# VL53L0X.net
KiCad netlist of a schematic drawn in Altium Designer
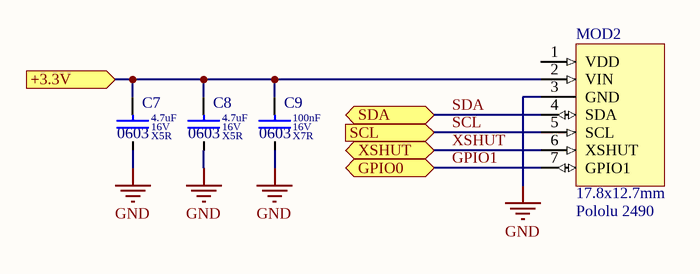
[diagram p0: VL53L0X.SchDoc]

(export (version "E")
  (design (tool "Eeschema 10.0.6"))
  (components
    (comp (ref "C7")
      (value "4.7uF")
      (footprint "C_0603_1608")
      (description "Capacitor")
      (fields
        (field (name "DIELECTRIC") "X5R")
        (field (name "VOLTAGE") "16V")
        (field (name "SCH_FOOTPRINT") "0603")
        (field (name "PART NUMBER") "C_4.7uF_16V_X5R_0603_10")
        (field (name "MANUFACTURER") "Murata")
      )
      (libsource (lib "Library") (part "C"))
    )
    (comp (ref "C8")
      (value "4.7uF")
      (footprint "C_0603_1608")
      (description "Capacitor")
      (fields
        (field (name "DIELECTRIC") "X5R")
        (field (name "VOLTAGE") "16V")
        (field (name "SCH_FOOTPRINT") "0603")
        (field (name "PART NUMBER") "C_4.7uF_16V_X5R_0603_10")
        (field (name "MANUFACTURER") "Murata")
      )
      (libsource (lib "Library") (part "C"))
    )
    (comp (ref "C9")
      (value "100nF")
      (footprint "C_0603_1608")
      (description "Capacitor")
      (fields
        (field (name "DIELECTRIC") "X7R")
        (field (name "VOLTAGE") "16V")
        (field (name "SCH_FOOTPRINT") "0603")
        (field (name "PART NUMBER") "C_100nF_16V_X7R_0603_10")
        (field (name "MANUFACTURER") "Kemet")
      )
      (libsource (lib "Library") (part "C"))
    )
    (comp (ref "MOD2")
      (value "Pololu 2490")
      (footprint "MOD_VL53L0X")
      (description "Pin Header")
      (fields
        (field (name "SCH_FOOTPRINT") "17.8x12.7mm")
        (field (name "PART NUMBER") "MOD_VL53L0X")
        (field (name "MANUFACTURER") "Polulu")
      )
      (libsource (lib "Library") (part "MOD_VL53L0X"))
    )
  )
  (nets
    (net (code "1") (name "/+3.3V") (class "Default")
      (node (ref "C7") (pin "1") (pinfunction "1_1") (pintype "passive"))
      (node (ref "C8") (pin "1") (pinfunction "1_1") (pintype "passive"))
      (node (ref "C9") (pin "1") (pinfunction "1_1") (pintype "passive"))
      (node (ref "MOD2") (pin "2") (pinfunction "VIN_2") (pintype "input"))
    )
    (net (code "2") (name "/GPIO1") (class "Default")
      (node (ref "MOD2") (pin "7") (pinfunction "GPIO1_7") (pintype "bidirectional"))
    )
    (net (code "3") (name "/SCL") (class "Default")
      (node (ref "MOD2") (pin "5") (pinfunction "SCL_5") (pintype "input"))
    )
    (net (code "4") (name "/SDA") (class "Default")
      (node (ref "MOD2") (pin "4") (pinfunction "SDA_4") (pintype "bidirectional"))
    )
    (net (code "5") (name "/XSHUT") (class "Default")
      (node (ref "MOD2") (pin "6") (pinfunction "XSHUT_6") (pintype "input"))
    )
    (net (code "6") (name "GND") (class "Default")
      (node (ref "C7") (pin "2") (pinfunction "2_2") (pintype "passive"))
      (node (ref "C8") (pin "2") (pinfunction "2_2") (pintype "passive"))
      (node (ref "C9") (pin "2") (pinfunction "2_2") (pintype "passive"))
      (node (ref "MOD2") (pin "3") (pinfunction "GND_3") (pintype "power_in"))
    )
    (net (code "7") (name "unconnected-(MOD2-VDD-Pad1)") (class "Default")
      (node (ref "MOD2") (pin "1") (pinfunction "VDD_1") (pintype "input"))
    )
  )
)
